# Bluetooth_Transmitter.net
KiCad netlist of a schematic drawn in Altium Designer
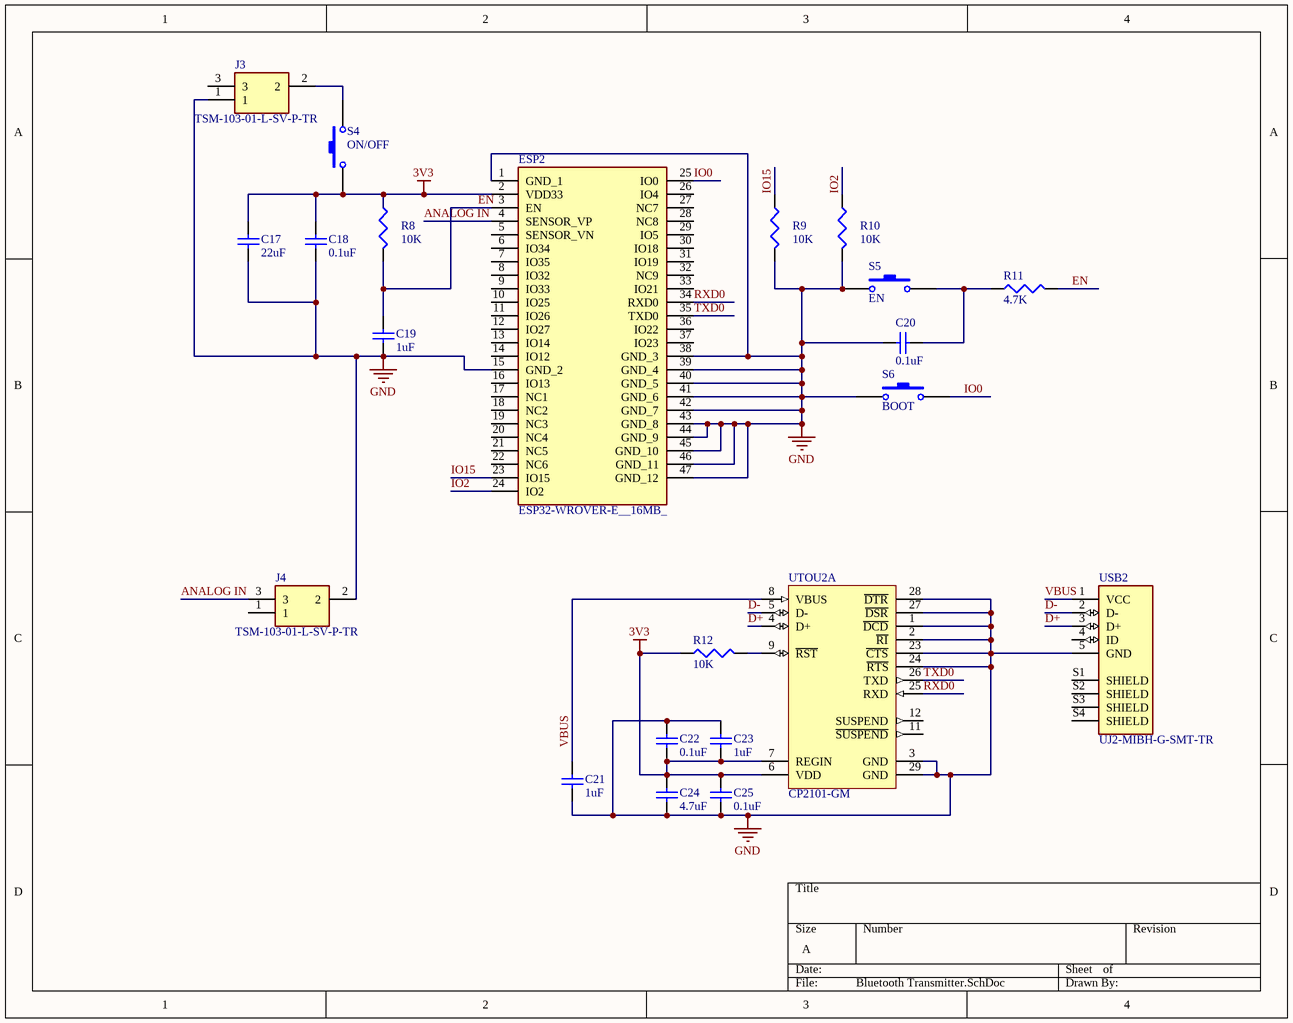
[diagram p0: Bluetooth Transmitter.SchDoc]

(export (version "E")
  (design (tool "Eeschema 10.0.6"))
  (components
    (comp (ref "C17")
      (value "22uF")
      (footprint "1608[0603]")
      (description "Capacitor (Semiconductor SIM Model)")
      (fields (field (name "Comment") "Cap") (field (name "PUBLISHER") "Altium Limited"))
      (libsource (lib "Miscellaneous Devices") (part "Cap Semi"))
    )
    (comp (ref "C18")
      (value "0.1uF")
      (footprint "1608[0603]")
      (description "Capacitor (Semiconductor SIM Model)")
      (fields (field (name "Comment") "Cap") (field (name "PUBLISHER") "Altium Limited"))
      (libsource (lib "Miscellaneous Devices") (part "Cap Semi"))
    )
    (comp (ref "C19")
      (value "1uF")
      (footprint "1608[0603]")
      (description "Capacitor (Semiconductor SIM Model)")
      (fields (field (name "Comment") "Cap") (field (name "PUBLISHER") "Altium Limited"))
      (libsource (lib "Miscellaneous Devices") (part "Cap Semi"))
    )
    (comp (ref "C20")
      (value "0.1uF")
      (footprint "1608[0603]")
      (description "Capacitor (Semiconductor SIM Model)")
      (fields (field (name "Comment") "Cap") (field (name "PUBLISHER") "Altium Limited"))
      (libsource (lib "Miscellaneous Devices") (part "Cap Semi"))
    )
    (comp (ref "C21")
      (value "1uF")
      (footprint "1608[0603]")
      (description "Capacitor (Semiconductor SIM Model)")
      (fields (field (name "Comment") "Cap") (field (name "PUBLISHER") "Altium Limited"))
      (libsource (lib "Miscellaneous Devices") (part "Cap Semi"))
    )
    (comp (ref "C22")
      (value "0.1uF")
      (footprint "1608[0603]")
      (description "Capacitor (Semiconductor SIM Model)")
      (fields (field (name "Comment") "Cap") (field (name "PUBLISHER") "Altium Limited"))
      (libsource (lib "Miscellaneous Devices") (part "Cap Semi"))
    )
    (comp (ref "C23")
      (value "1uF")
      (footprint "1608[0603]")
      (description "Capacitor (Semiconductor SIM Model)")
      (fields (field (name "Comment") "Cap") (field (name "PUBLISHER") "Altium Limited"))
      (libsource (lib "Miscellaneous Devices") (part "Cap Semi"))
    )
    (comp (ref "C24")
      (value "4.7uF")
      (footprint "1608[0603]")
      (description "Capacitor (Semiconductor SIM Model)")
      (fields (field (name "Comment") "Cap") (field (name "PUBLISHER") "Altium Limited"))
      (libsource (lib "Miscellaneous Devices") (part "Cap Semi"))
    )
    (comp (ref "C25")
      (value "0.1uF")
      (footprint "1608[0603]")
      (description "Capacitor (Semiconductor SIM Model)")
      (fields (field (name "Comment") "Cap") (field (name "PUBLISHER") "Altium Limited"))
      (libsource (lib "Miscellaneous Devices") (part "Cap Semi"))
    )
    (comp (ref "ESP2")
      (value "ESP32-WROVER-E__16MB_")
      (footprint "SamacSys:ESP32WROVERE16MB")
      (description "Integrated Circuit")
      (fields
        (field (name "MANUFACTURER_PART_NUMBER") "ESP32-WROVER-E (16MB)")
        (field (name "MOUSER PART NUMBER") "356-ESP32WRVE22864PC")
      )
      (libsource (lib "*") (part "ESP32-WROVER-E__16MB_"))
    )
    (comp (ref "J3")
      (value "TSM-103-01-L-SV-P-TR")
      (footprint "SamacSys:TSM10301LSVPTR")
      (description "Connector")
      (fields (field (name "MOUSER PART NUMBER") "200-TSM10301LSVPTR"))
      (libsource (lib "*") (part "TSM-103-01-L-SV-P-TR"))
    )
    (comp (ref "J4")
      (value "TSM-103-01-L-SV-P-TR")
      (footprint "SamacSys:TSM10301LSVPTR")
      (description "Connector")
      (fields (field (name "MOUSER PART NUMBER") "200-TSM10301LSVPTR"))
      (libsource (lib "*") (part "TSM-103-01-L-SV-P-TR"))
    )
    (comp (ref "R8")
      (value "10K")
      (footprint "J1-0603")
      (description "Resistor")
      (fields (field (name "Comment") "Res3") (field (name "PUBLISHER") "Altium Limited"))
      (libsource (lib "Miscellaneous Devices") (part "Res3"))
    )
    (comp (ref "R9")
      (value "10K")
      (footprint "J1-0603")
      (description "Resistor")
      (fields (field (name "Comment") "Res3") (field (name "PUBLISHER") "Altium Limited"))
      (libsource (lib "Miscellaneous Devices") (part "Res3"))
    )
    (comp (ref "R10")
      (value "10K")
      (footprint "J1-0603")
      (description "Resistor")
      (fields (field (name "Comment") "Res3") (field (name "PUBLISHER") "Altium Limited"))
      (libsource (lib "Miscellaneous Devices") (part "Res3"))
    )
    (comp (ref "R11")
      (value "4.7K")
      (footprint "J1-0603")
      (description "Resistor")
      (fields (field (name "Comment") "Res3") (field (name "PUBLISHER") "Altium Limited"))
      (libsource (lib "Miscellaneous Devices") (part "Res3"))
    )
    (comp (ref "R12")
      (value "10K")
      (footprint "J1-0603")
      (description "Resistor")
      (fields (field (name "Comment") "Res3") (field (name "PUBLISHER") "Altium Limited"))
      (libsource (lib "Miscellaneous Devices") (part "Res3"))
    )
    (comp (ref "S4")
      (value "ON/OFF")
      (footprint "R1966ABLKBLKEF:R1966ABLKBLKEF")
      (description "Switch")
      (fields (field (name "PUBLISHER") "Altium Limited"))
      (libsource (lib "Miscellaneous Devices") (part "SW-PB"))
    )
    (comp (ref "S5")
      (value "EN")
      (footprint "R1966ABLKBLKEF:R1966ABLKBLKEF")
      (description "Switch")
      (fields (field (name "PUBLISHER") "Altium Limited"))
      (libsource (lib "Miscellaneous Devices") (part "SW-PB"))
    )
    (comp (ref "S6")
      (value "BOOT")
      (footprint "R1966ABLKBLKEF:R1966ABLKBLKEF")
      (description "Switch")
      (fields (field (name "PUBLISHER") "Altium Limited"))
      (libsource (lib "Miscellaneous Devices") (part "SW-PB"))
    )
    (comp (ref "USB2")
      (value "UJ2-MIBH-G-SMT-TR")
      (footprint "CUI_UJ2-MIBH-G-SMT-TR:CUI_UJ2-MIBH-G-SMT-TR")
      (description "USB micro B type receptacle")
      (libsource (lib "UJ2-MIBH-G-SMT-TR") (part "UJ2-MIBH-G-SMT-TR"))
    )
    (comp (ref "UTOU2")
      (value "CP2101-GM")
      (footprint "Silicon_Labs_CP2101_GM_0:SLAB-QFN-28-3125x3125TP_A_N")
      (description "Single-Chip USB to UART Bridge, 512 Bytes EEPROM, -40 to 85 degC, 28-pin QFN, Tube")
      (fields (field (name "MANUFACTURER") "Silicon Labs"))
      (libsource (lib "Silicon_Labs_CP2101_GM") (part "CP2101-GM"))
    )
  )
  (nets
    (net (code "1") (name "/ANALOG IN") (class "Default")
      (node (ref "ESP2") (pin "4") (pinfunction "SENSOR_VP_4") (pintype "passive"))
      (node (ref "J4") (pin "3") (pinfunction "3_3") (pintype "passive"))
    )
    (net (code "2") (name "/D+") (class "Default")
      (node (ref "USB2") (pin "3") (pinfunction "D+_3") (pintype "bidirectional"))
      (node (ref "UTOU2") (pin "4") (pinfunction "D+_4") (pintype "bidirectional"))
    )
    (net (code "3") (name "/D-") (class "Default")
      (node (ref "USB2") (pin "2") (pinfunction "D-_2") (pintype "bidirectional"))
      (node (ref "UTOU2") (pin "5") (pinfunction "D-_5") (pintype "bidirectional"))
    )
    (net (code "4") (name "/EN") (class "Default")
      (node (ref "C19") (pin "2") (pinfunction "2_2") (pintype "passive"))
      (node (ref "ESP2") (pin "3") (pinfunction "EN_3") (pintype "passive"))
      (node (ref "R11") (pin "2") (pinfunction "2_2") (pintype "passive"))
      (node (ref "R8") (pin "2") (pinfunction "2_2") (pintype "passive"))
    )
    (net (code "5") (name "/IO0") (class "Default")
      (node (ref "ESP2") (pin "25") (pinfunction "IO0_25") (pintype "passive"))
      (node (ref "S6") (pin "2") (pinfunction "2_2") (pintype "passive"))
    )
    (net (code "6") (name "/IO2") (class "Default")
      (node (ref "ESP2") (pin "24") (pinfunction "IO2_24") (pintype "passive"))
      (node (ref "R10") (pin "1") (pinfunction "1_1") (pintype "passive"))
    )
    (net (code "7") (name "/IO15") (class "Default")
      (node (ref "ESP2") (pin "23") (pinfunction "IO15_23") (pintype "passive"))
      (node (ref "R9") (pin "1") (pinfunction "1_1") (pintype "passive"))
    )
    (net (code "8") (name "/RXD0") (class "Default")
      (node (ref "ESP2") (pin "34") (pinfunction "RXD0_34") (pintype "passive"))
      (node (ref "UTOU2") (pin "25") (pinfunction "RXD_25") (pintype "input"))
    )
    (net (code "9") (name "/TXD0") (class "Default")
      (node (ref "ESP2") (pin "35") (pinfunction "TXD0_35") (pintype "passive"))
      (node (ref "UTOU2") (pin "26") (pinfunction "TXD_26") (pintype "output"))
    )
    (net (code "10") (name "/VBUS") (class "Default")
      (node (ref "C21") (pin "2") (pinfunction "2_2") (pintype "passive"))
      (node (ref "USB2") (pin "1") (pinfunction "VCC_1") (pintype "power_in"))
      (node (ref "UTOU2") (pin "8") (pinfunction "VBUS_8") (pintype "input"))
    )
    (net (code "11") (name "3V3") (class "Default")
      (node (ref "C17") (pin "2") (pinfunction "2_2") (pintype "passive"))
      (node (ref "C18") (pin "2") (pinfunction "2_2") (pintype "passive"))
      (node (ref "C22") (pin "1") (pinfunction "1_1") (pintype "passive"))
      (node (ref "C23") (pin "1") (pinfunction "1_1") (pintype "passive"))
      (node (ref "C24") (pin "2") (pinfunction "2_2") (pintype "passive"))
      (node (ref "C25") (pin "2") (pinfunction "2_2") (pintype "passive"))
      (node (ref "ESP2") (pin "2") (pinfunction "VDD33_2") (pintype "passive"))
      (node (ref "R12") (pin "1") (pinfunction "1_1") (pintype "passive"))
      (node (ref "R8") (pin "1") (pinfunction "1_1") (pintype "passive"))
      (node (ref "S4") (pin "1") (pinfunction "1_1") (pintype "passive"))
      (node (ref "UTOU2") (pin "6") (pinfunction "VDD_6") (pintype "power_in"))
      (node (ref "UTOU2") (pin "7") (pinfunction "REGIN_7") (pintype "power_in"))
    )
    (net (code "12") (name "GND") (class "Default")
      (node (ref "C17") (pin "1") (pinfunction "1_1") (pintype "passive"))
      (node (ref "C18") (pin "1") (pinfunction "1_1") (pintype "passive"))
      (node (ref "C19") (pin "1") (pinfunction "1_1") (pintype "passive"))
      (node (ref "C20") (pin "2") (pinfunction "2_2") (pintype "passive"))
      (node (ref "C21") (pin "1") (pinfunction "1_1") (pintype "passive"))
      (node (ref "C22") (pin "2") (pinfunction "2_2") (pintype "passive"))
      (node (ref "C23") (pin "2") (pinfunction "2_2") (pintype "passive"))
      (node (ref "C24") (pin "1") (pinfunction "1_1") (pintype "passive"))
      (node (ref "C25") (pin "1") (pinfunction "1_1") (pintype "passive"))
      (node (ref "ESP2") (pin "1") (pinfunction "GND_1_1") (pintype "passive"))
      (node (ref "ESP2") (pin "15") (pinfunction "GND_2_15") (pintype "passive"))
      (node (ref "ESP2") (pin "38") (pinfunction "GND_3_38") (pintype "passive"))
      (node (ref "ESP2") (pin "39") (pinfunction "GND_4_39") (pintype "passive"))
      (node (ref "ESP2") (pin "40") (pinfunction "GND_5_40") (pintype "passive"))
      (node (ref "ESP2") (pin "41") (pinfunction "GND_6_41") (pintype "passive"))
      (node (ref "ESP2") (pin "42") (pinfunction "GND_7_42") (pintype "passive"))
      (node (ref "ESP2") (pin "43") (pinfunction "GND_8_43") (pintype "passive"))
      (node (ref "ESP2") (pin "44") (pinfunction "GND_9_44") (pintype "passive"))
      (node (ref "ESP2") (pin "45") (pinfunction "GND_10_45") (pintype "passive"))
      (node (ref "ESP2") (pin "46") (pinfunction "GND_11_46") (pintype "passive"))
      (node (ref "ESP2") (pin "47") (pinfunction "GND_12_47") (pintype "passive"))
      (node (ref "J3") (pin "1") (pinfunction "1_1") (pintype "passive"))
      (node (ref "J4") (pin "2") (pinfunction "2_2") (pintype "passive"))
      (node (ref "R10") (pin "2") (pinfunction "2_2") (pintype "passive"))
      (node (ref "R9") (pin "2") (pinfunction "2_2") (pintype "passive"))
      (node (ref "S5") (pin "1") (pinfunction "1_1") (pintype "passive"))
      (node (ref "S6") (pin "1") (pinfunction "1_1") (pintype "passive"))
      (node (ref "USB2") (pin "5") (pinfunction "GND_5") (pintype "power_in"))
      (node (ref "UTOU2") (pin "1") (pinfunction "~{DCD}_1") (pintype "passive"))
      (node (ref "UTOU2") (pin "2") (pinfunction "~{RI}_2") (pintype "passive"))
      (node (ref "UTOU2") (pin "23") (pinfunction "~{CTS}_23") (pintype "passive"))
      (node (ref "UTOU2") (pin "24") (pinfunction "~{RTS}_24") (pintype "passive"))
      (node (ref "UTOU2") (pin "27") (pinfunction "~{DSR}_27") (pintype "passive"))
      (node (ref "UTOU2") (pin "28") (pinfunction "~{DTR}_28") (pintype "passive"))
      (node (ref "UTOU2") (pin "29") (pinfunction "GND_29") (pintype "power_in"))
      (node (ref "UTOU2") (pin "3") (pinfunction "GND_3") (pintype "power_in"))
    )
    (net (code "13") (name "Net-(C20-Pad1)") (class "Default")
      (node (ref "C20") (pin "1") (pinfunction "1_1") (pintype "passive"))
      (node (ref "R11") (pin "1") (pinfunction "1_1") (pintype "passive"))
      (node (ref "S5") (pin "2") (pinfunction "2_2") (pintype "passive"))
    )
    (net (code "14") (name "Net-(J3-Pad2)") (class "Default")
      (node (ref "J3") (pin "2") (pinfunction "2_2") (pintype "passive"))
      (node (ref "S4") (pin "2") (pinfunction "2_2") (pintype "passive"))
    )
    (net (code "15") (name "Net-(UTOU2A-~{RST})") (class "Default")
      (node (ref "R12") (pin "2") (pinfunction "2_2") (pintype "passive"))
      (node (ref "UTOU2") (pin "9") (pinfunction "~{RST}_9") (pintype "bidirectional"))
    )
    (net (code "16") (name "unconnected-(ESP2-IO4-Pad26)") (class "Default")
      (node (ref "ESP2") (pin "26") (pinfunction "IO4_26") (pintype "passive"))
    )
    (net (code "17") (name "unconnected-(ESP2-IO5-Pad29)") (class "Default")
      (node (ref "ESP2") (pin "29") (pinfunction "IO5_29") (pintype "passive"))
    )
    (net (code "18") (name "unconnected-(ESP2-IO12-Pad14)") (class "Default")
      (node (ref "ESP2") (pin "14") (pinfunction "IO12_14") (pintype "passive"))
    )
    (net (code "19") (name "unconnected-(ESP2-IO13-Pad16)") (class "Default")
      (node (ref "ESP2") (pin "16") (pinfunction "IO13_16") (pintype "passive"))
    )
    (net (code "20") (name "unconnected-(ESP2-IO14-Pad13)") (class "Default")
      (node (ref "ESP2") (pin "13") (pinfunction "IO14_13") (pintype "passive"))
    )
    (net (code "21") (name "unconnected-(ESP2-IO18-Pad30)") (class "Default")
      (node (ref "ESP2") (pin "30") (pinfunction "IO18_30") (pintype "passive"))
    )
    (net (code "22") (name "unconnected-(ESP2-IO19-Pad31)") (class "Default")
      (node (ref "ESP2") (pin "31") (pinfunction "IO19_31") (pintype "passive"))
    )
    (net (code "23") (name "unconnected-(ESP2-IO21-Pad33)") (class "Default")
      (node (ref "ESP2") (pin "33") (pinfunction "IO21_33") (pintype "passive"))
    )
    (net (code "24") (name "unconnected-(ESP2-IO22-Pad36)") (class "Default")
      (node (ref "ESP2") (pin "36") (pinfunction "IO22_36") (pintype "passive"))
    )
    (net (code "25") (name "unconnected-(ESP2-IO23-Pad37)") (class "Default")
      (node (ref "ESP2") (pin "37") (pinfunction "IO23_37") (pintype "passive"))
    )
    (net (code "26") (name "unconnected-(ESP2-IO25-Pad10)") (class "Default")
      (node (ref "ESP2") (pin "10") (pinfunction "IO25_10") (pintype "passive"))
    )
    (net (code "27") (name "unconnected-(ESP2-IO26-Pad11)") (class "Default")
      (node (ref "ESP2") (pin "11") (pinfunction "IO26_11") (pintype "passive"))
    )
    (net (code "28") (name "unconnected-(ESP2-IO27-Pad12)") (class "Default")
      (node (ref "ESP2") (pin "12") (pinfunction "IO27_12") (pintype "passive"))
    )
    (net (code "29") (name "unconnected-(ESP2-IO32-Pad8)") (class "Default")
      (node (ref "ESP2") (pin "8") (pinfunction "IO32_8") (pintype "passive"))
    )
    (net (code "30") (name "unconnected-(ESP2-IO33-Pad9)") (class "Default")
      (node (ref "ESP2") (pin "9") (pinfunction "IO33_9") (pintype "passive"))
    )
    (net (code "31") (name "unconnected-(ESP2-IO34-Pad6)") (class "Default")
      (node (ref "ESP2") (pin "6") (pinfunction "IO34_6") (pintype "passive"))
    )
    (net (code "32") (name "unconnected-(ESP2-IO35-Pad7)") (class "Default")
      (node (ref "ESP2") (pin "7") (pinfunction "IO35_7") (pintype "passive"))
    )
    (net (code "33") (name "unconnected-(ESP2-NC1-Pad17)") (class "Default")
      (node (ref "ESP2") (pin "17") (pinfunction "NC1_17") (pintype "passive"))
    )
    (net (code "34") (name "unconnected-(ESP2-NC2-Pad18)") (class "Default")
      (node (ref "ESP2") (pin "18") (pinfunction "NC2_18") (pintype "passive"))
    )
    (net (code "35") (name "unconnected-(ESP2-NC3-Pad19)") (class "Default")
      (node (ref "ESP2") (pin "19") (pinfunction "NC3_19") (pintype "passive"))
    )
    (net (code "36") (name "unconnected-(ESP2-NC4-Pad20)") (class "Default")
      (node (ref "ESP2") (pin "20") (pinfunction "NC4_20") (pintype "passive"))
    )
    (net (code "37") (name "unconnected-(ESP2-NC5-Pad21)") (class "Default")
      (node (ref "ESP2") (pin "21") (pinfunction "NC5_21") (pintype "passive"))
    )
    (net (code "38") (name "unconnected-(ESP2-NC6-Pad22)") (class "Default")
      (node (ref "ESP2") (pin "22") (pinfunction "NC6_22") (pintype "passive"))
    )
    (net (code "39") (name "unconnected-(ESP2-NC7-Pad27)") (class "Default")
      (node (ref "ESP2") (pin "27") (pinfunction "NC7_27") (pintype "passive"))
    )
    (net (code "40") (name "unconnected-(ESP2-NC8-Pad28)") (class "Default")
      (node (ref "ESP2") (pin "28") (pinfunction "NC8_28") (pintype "passive"))
    )
    (net (code "41") (name "unconnected-(ESP2-NC9-Pad32)") (class "Default")
      (node (ref "ESP2") (pin "32") (pinfunction "NC9_32") (pintype "passive"))
    )
    (net (code "42") (name "unconnected-(ESP2-SENSOR_VN-Pad5)") (class "Default")
      (node (ref "ESP2") (pin "5") (pinfunction "SENSOR_VN_5") (pintype "passive"))
    )
    (net (code "43") (name "unconnected-(J3-Pad3)") (class "Default")
      (node (ref "J3") (pin "3") (pinfunction "3_3") (pintype "passive"))
    )
    (net (code "44") (name "unconnected-(J4-Pad1)") (class "Default")
      (node (ref "J4") (pin "1") (pinfunction "1_1") (pintype "passive"))
    )
    (net (code "45") (name "unconnected-(USB2-ID-Pad4)") (class "Default")
      (node (ref "USB2") (pin "4") (pinfunction "ID_4") (pintype "bidirectional"))
    )
    (net (code "46") (name "unconnected-(USB2-SHIELD-PadS1)") (class "Default")
      (node (ref "USB2") (pin "S1") (pinfunction "SHIELD_S1") (pintype "passive"))
    )
    (net (code "47") (name "unconnected-(USB2-SHIELD-PadS2)") (class "Default")
      (node (ref "USB2") (pin "S2") (pinfunction "SHIELD_S2") (pintype "passive"))
    )
    (net (code "48") (name "unconnected-(USB2-SHIELD-PadS3)") (class "Default")
      (node (ref "USB2") (pin "S3") (pinfunction "SHIELD_S3") (pintype "passive"))
    )
    (net (code "49") (name "unconnected-(USB2-SHIELD-PadS4)") (class "Default")
      (node (ref "USB2") (pin "S4") (pinfunction "SHIELD_S4") (pintype "passive"))
    )
    (net (code "50") (name "unconnected-(UTOU2A-SUSPEND-Pad12)") (class "Default")
      (node (ref "UTOU2") (pin "12") (pinfunction "SUSPEND_12") (pintype "output"))
    )
    (net (code "51") (name "unconnected-(UTOU2A-~{SUSPEND}-Pad11)") (class "Default")
      (node (ref "UTOU2") (pin "11") (pinfunction "~{SUSPEND}_11") (pintype "output"))
    )
  )
)
